# EASY_EDA_Neurostim.net
KiCad netlist of a schematic drawn in EasyEDA
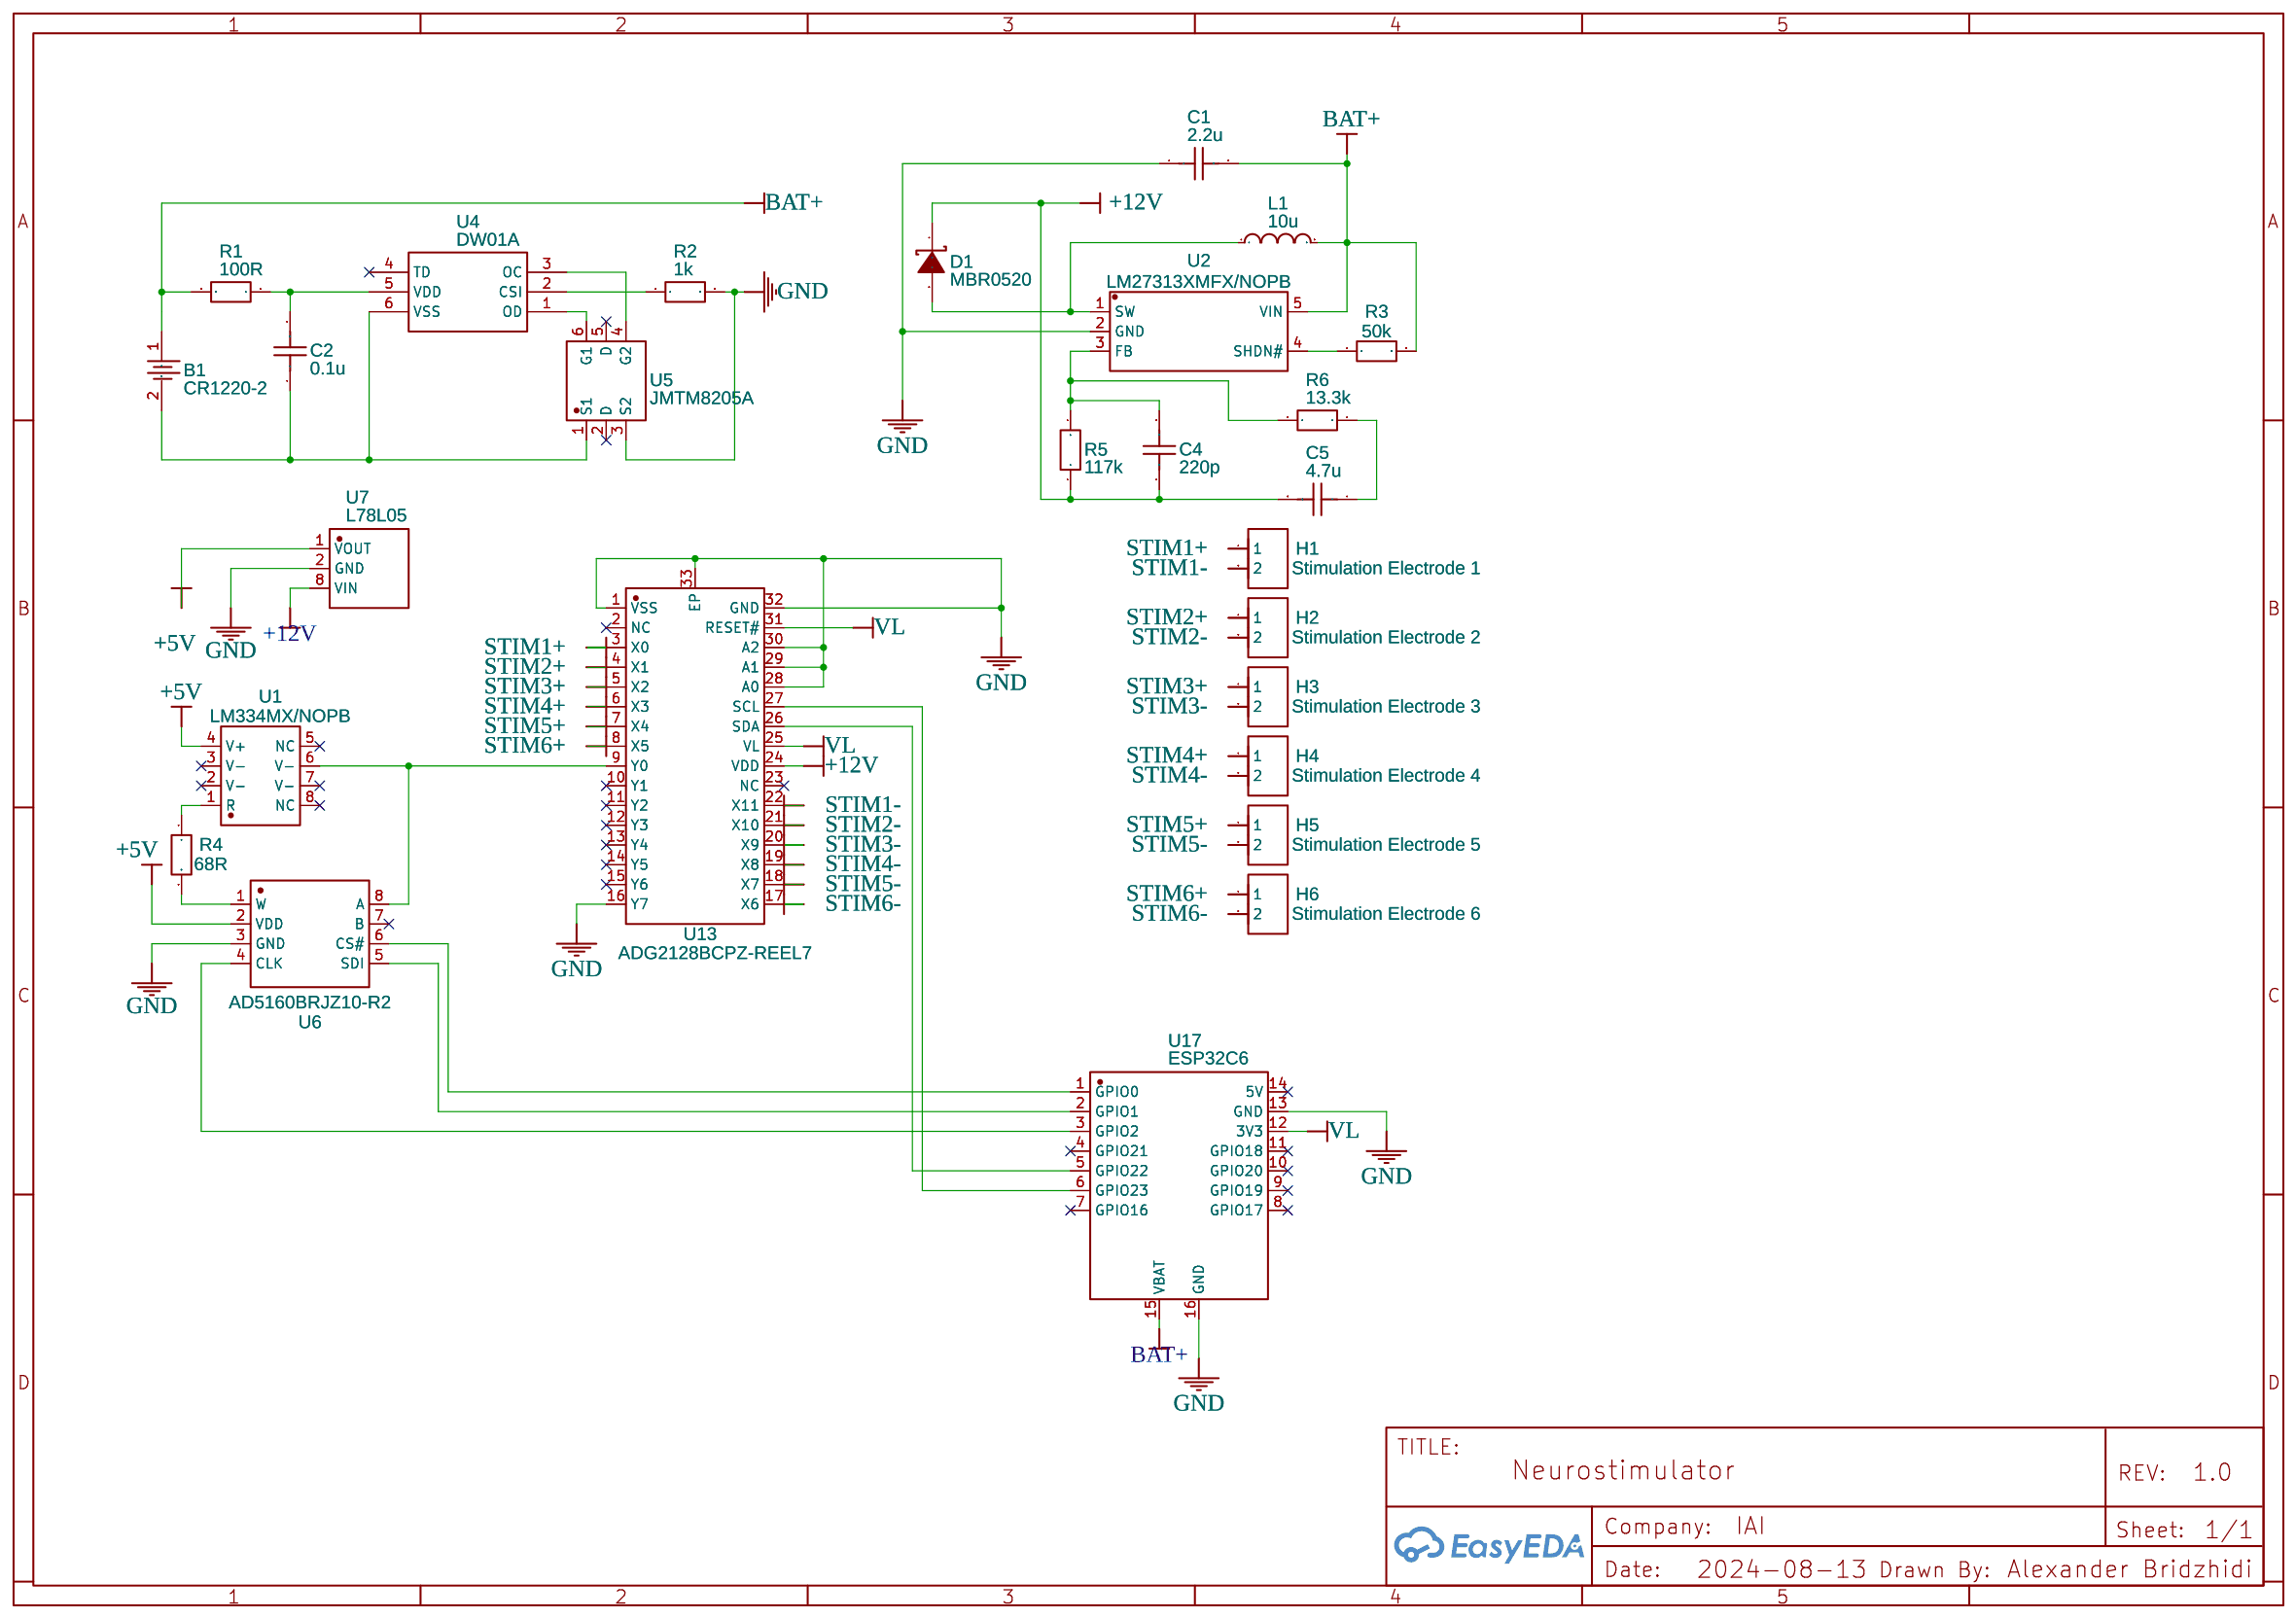
[diagram p0: 5V]
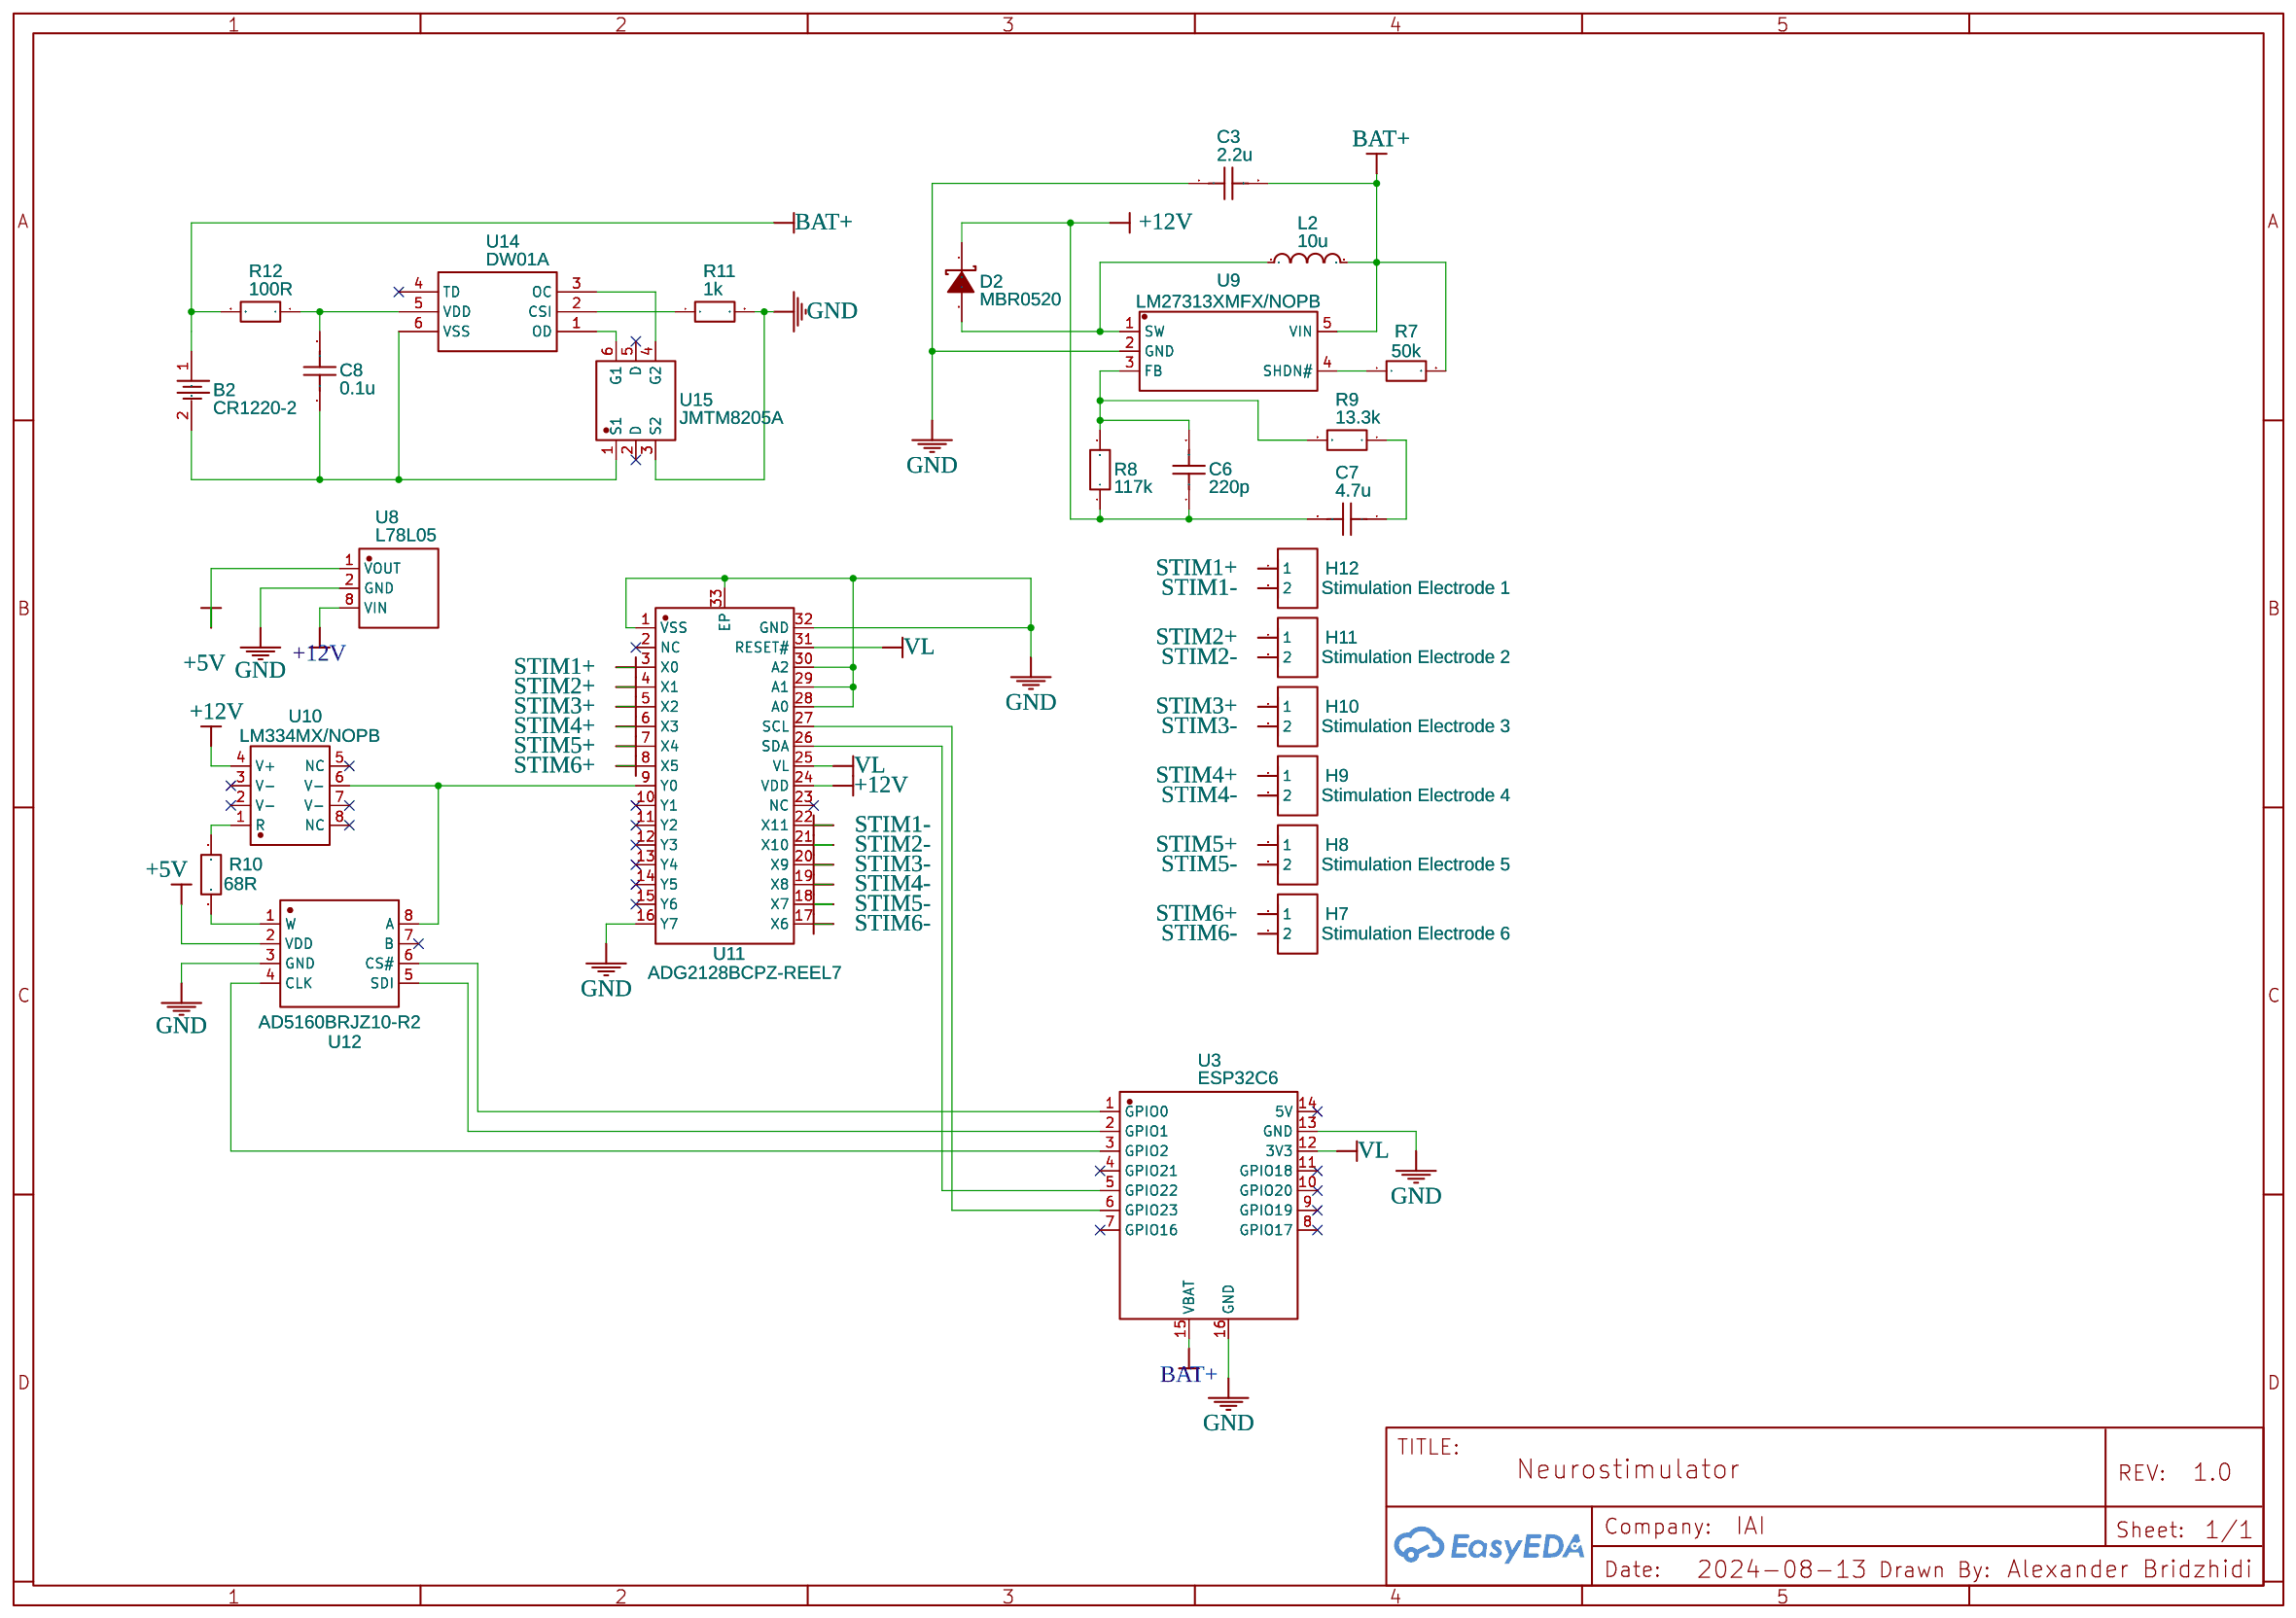
[diagram p1: 12V]

(export (version "E")
  (design (tool "Eeschema 10.0.6"))
  (components
    (comp (ref "B1")
      (value "CR1220-2")
      (fields (field (name "Manufacturer") "Q&J"))
      (libsource (lib "") (part "CR1220-2"))
    )
    (comp (ref "C1") (value "2.2u") (libsource (lib "") (part "C_0603_US_2")))
    (comp (ref "C2") (value "0.1u") (libsource (lib "") (part "C_0603_US")))
    (comp (ref "C4") (value "220p") (libsource (lib "") (part "C_0603_US")))
    (comp (ref "C5") (value "4.7u") (libsource (lib "") (part "C_0603_US_1")))
    (comp (ref "D1")
      (value "MBR0520")
      (fields (field (name "Manufacturer") "CJ(江苏长电/长晶)"))
      (libsource (lib "") (part "MBR0520"))
    )
    (comp (ref "H1") (value "Stimulation Electrode 1") (libsource (lib "") (part "HDR-F-2.54_1x2")))
    (comp (ref "H2") (value "Stimulation Electrode 2") (libsource (lib "") (part "HDR-F-2.54_1x2")))
    (comp (ref "H3") (value "Stimulation Electrode 3") (libsource (lib "") (part "HDR-F-2.54_1x2")))
    (comp (ref "H4") (value "Stimulation Electrode 4") (libsource (lib "") (part "HDR-F-2.54_1x2")))
    (comp (ref "H5") (value "Stimulation Electrode 5") (libsource (lib "") (part "HDR-F-2.54_1x2")))
    (comp (ref "H6") (value "Stimulation Electrode 6") (libsource (lib "") (part "HDR-F-2.54_1x2")))
    (comp (ref "L1") (value "10u") (libsource (lib "") (part "L0603_US")))
    (comp (ref "R1") (value "100R") (libsource (lib "") (part "R_0603_EU_1")))
    (comp (ref "R2") (value "1k") (libsource (lib "") (part "R_0603_EU_2")))
    (comp (ref "R3") (value "50k") (libsource (lib "") (part "R_0603_EU_2")))
    (comp (ref "R4") (value "68R") (libsource (lib "") (part "R_0805_EU")))
    (comp (ref "R5") (value "117k") (libsource (lib "") (part "R_0603_EU")))
    (comp (ref "R6") (value "13.3k") (libsource (lib "") (part "R_0603_EU_1")))
    (comp (ref "U1")
      (value "LM334MX/NOPB")
      (fields (field (name "Manufacturer") "TI(德州仪器)"))
      (libsource (lib "") (part "LM334MX/NOPB"))
    )
    (comp (ref "U2")
      (value "LM27313XMFX/NOPB")
      (fields (field (name "Manufacturer") "TI(德州仪器)"))
      (libsource (lib "") (part "LM27313XMFX/NOPB"))
    )
    (comp (ref "U4") (value "DW01A") (libsource (lib "") (part "DW01A")))
    (comp (ref "U5")
      (value "JMTM8205A")
      (fields (field (name "Manufacturer") "JJW(捷捷微)"))
      (libsource (lib "") (part "JMTM8205A"))
    )
    (comp (ref "U6")
      (value "AD5160BRJZ10-R2")
      (fields (field (name "Manufacturer") "ADI(亚德诺)"))
      (libsource (lib "") (part "AD5160BRJZ10-R2"))
    )
    (comp (ref "U7")
      (value "L78L05")
      (fields (field (name "Manufacturer Part") "L78L05ACZ-AP") (field (name "Manufacturer") "ST(意法半导体)"))
      (libsource (lib "") (part "L78L05ACZ-AP"))
    )
    (comp (ref "U13")
      (value "ADG2128BCPZ-REEL7")
      (fields (field (name "Manufacturer") "ADI(亚德诺)"))
      (libsource (lib "") (part "ADG2128BCPZ-REEL7"))
    )
    (comp (ref "U17") (value "ESP32C6") (libsource (lib "") (part "ESP32C6")))
    (comp (ref "B2")
      (value "CR1220-2")
      (fields (field (name "Manufacturer") "Q&J"))
      (libsource (lib "") (part "CR1220-2"))
    )
    (comp (ref "C3") (value "2.2u") (libsource (lib "") (part "C_0603_US_2")))
    (comp (ref "C6") (value "220p") (libsource (lib "") (part "C_0603_US_1")))
    (comp (ref "C7") (value "4.7u") (libsource (lib "") (part "C_0603_US")))
    (comp (ref "C8") (value "0.1u") (libsource (lib "") (part "C_0603_US_1")))
    (comp (ref "D2")
      (value "MBR0520")
      (fields (field (name "Manufacturer") "CJ(江苏长电/长晶)"))
      (libsource (lib "") (part "MBR0520"))
    )
    (comp (ref "H7") (value "Stimulation Electrode 6") (libsource (lib "") (part "HDR-F-2.54_1x2")))
    (comp (ref "H8") (value "Stimulation Electrode 5") (libsource (lib "") (part "HDR-F-2.54_1x2")))
    (comp (ref "H9") (value "Stimulation Electrode 4") (libsource (lib "") (part "HDR-F-2.54_1x2")))
    (comp (ref "H10") (value "Stimulation Electrode 3") (libsource (lib "") (part "HDR-F-2.54_1x2")))
    (comp (ref "H11") (value "Stimulation Electrode 2") (libsource (lib "") (part "HDR-F-2.54_1x2")))
    (comp (ref "H12") (value "Stimulation Electrode 1") (libsource (lib "") (part "HDR-F-2.54_1x2")))
    (comp (ref "L2") (value "10u") (libsource (lib "") (part "L0603_US")))
    (comp (ref "R7") (value "50k") (libsource (lib "") (part "R_0603_EU_1")))
    (comp (ref "R8") (value "117k") (libsource (lib "") (part "R_0603_EU_2")))
    (comp (ref "R9") (value "13.3k") (libsource (lib "") (part "R_0603_EU")))
    (comp (ref "R10") (value "68R") (libsource (lib "") (part "R_0805_EU")))
    (comp (ref "R11") (value "1k") (libsource (lib "") (part "R_0603_EU_1")))
    (comp (ref "R12") (value "100R") (libsource (lib "") (part "R_0603_EU")))
    (comp (ref "U3") (value "ESP32C6") (libsource (lib "") (part "ESP32C6")))
    (comp (ref "U8")
      (value "L78L05")
      (fields (field (name "Manufacturer Part") "L78L05ACZ-AP") (field (name "Manufacturer") "ST(意法半导体)"))
      (libsource (lib "") (part "L78L05ACZ-AP"))
    )
    (comp (ref "U9")
      (value "LM27313XMFX/NOPB")
      (fields (field (name "Manufacturer") "TI(德州仪器)"))
      (libsource (lib "") (part "LM27313XMFX/NOPB"))
    )
    (comp (ref "U10")
      (value "LM334MX/NOPB")
      (fields (field (name "Manufacturer") "TI(德州仪器)"))
      (libsource (lib "") (part "LM334MX/NOPB"))
    )
    (comp (ref "U11")
      (value "ADG2128BCPZ-REEL7")
      (fields (field (name "Manufacturer") "ADI(亚德诺)"))
      (libsource (lib "") (part "ADG2128BCPZ-REEL7"))
    )
    (comp (ref "U12")
      (value "AD5160BRJZ10-R2")
      (fields (field (name "Manufacturer") "ADI(亚德诺)"))
      (libsource (lib "") (part "AD5160BRJZ10-R2"))
    )
    (comp (ref "U14") (value "DW01A") (libsource (lib "") (part "DW01A")))
    (comp (ref "U15")
      (value "JMTM8205A")
      (fields (field (name "Manufacturer") "JJW(捷捷微)"))
      (libsource (lib "") (part "JMTM8205A"))
    )
  )
  (nets
    (net (code "1") (name "+5V") (class "Default")
      (node (ref "U1") (pin "4") (pinfunction "V+_4") (pintype "unspecified"))
      (node (ref "U12") (pin "2") (pinfunction "VDD_2") (pintype "unspecified"))
      (node (ref "U6") (pin "2") (pinfunction "VDD_2") (pintype "unspecified"))
      (node (ref "U7") (pin "1") (pinfunction "VOUT_1") (pintype "unspecified"))
      (node (ref "U8") (pin "1") (pinfunction "VOUT_1") (pintype "unspecified"))
    )
    (net (code "2") (name "+12V") (class "Default")
      (node (ref "C4") (pin "1") (pinfunction "1_1") (pintype "unspecified"))
      (node (ref "C5") (pin "2") (pinfunction "2_2") (pintype "unspecified"))
      (node (ref "C6") (pin "1") (pinfunction "1_1") (pintype "unspecified"))
      (node (ref "C7") (pin "2") (pinfunction "2_2") (pintype "unspecified"))
      (node (ref "D1") (pin "1") (pinfunction "K_1") (pintype "unspecified"))
      (node (ref "D2") (pin "1") (pinfunction "K_1") (pintype "unspecified"))
      (node (ref "R5") (pin "1") (pinfunction "1_1") (pintype "unspecified"))
      (node (ref "R8") (pin "1") (pinfunction "1_1") (pintype "unspecified"))
      (node (ref "U10") (pin "4") (pinfunction "V+_4") (pintype "unspecified"))
      (node (ref "U11") (pin "24") (pinfunction "VDD_24") (pintype "unspecified"))
      (node (ref "U13") (pin "24") (pinfunction "VDD_24") (pintype "unspecified"))
      (node (ref "U7") (pin "8") (pinfunction "VIN_8") (pintype "unspecified"))
      (node (ref "U8") (pin "8") (pinfunction "VIN_8") (pintype "unspecified"))
    )
    (net (code "3") (name "BAT+") (class "Default")
      (node (ref "B1") (pin "1") (pinfunction "1_1") (pintype "input"))
      (node (ref "B2") (pin "1") (pinfunction "1_1") (pintype "input"))
      (node (ref "C1") (pin "2") (pinfunction "2_2") (pintype "unspecified"))
      (node (ref "C3") (pin "2") (pinfunction "2_2") (pintype "unspecified"))
      (node (ref "L1") (pin "2") (pinfunction "2_2") (pintype "unspecified"))
      (node (ref "L2") (pin "2") (pinfunction "2_2") (pintype "unspecified"))
      (node (ref "R1") (pin "2") (pinfunction "2_2") (pintype "unspecified"))
      (node (ref "R12") (pin "2") (pinfunction "2_2") (pintype "unspecified"))
      (node (ref "R3") (pin "2") (pinfunction "2_2") (pintype "unspecified"))
      (node (ref "R7") (pin "2") (pinfunction "2_2") (pintype "unspecified"))
      (node (ref "U17") (pin "15") (pinfunction "VBAT_15") (pintype "unspecified"))
      (node (ref "U2") (pin "5") (pinfunction "VIN_5") (pintype "unspecified"))
      (node (ref "U3") (pin "15") (pinfunction "VBAT_15") (pintype "unspecified"))
      (node (ref "U9") (pin "5") (pinfunction "VIN_5") (pintype "unspecified"))
    )
    (net (code "4") (name "GND") (class "Default")
      (node (ref "C1") (pin "1") (pinfunction "1_1") (pintype "unspecified"))
      (node (ref "C3") (pin "1") (pinfunction "1_1") (pintype "unspecified"))
      (node (ref "R11") (pin "2") (pinfunction "2_2") (pintype "unspecified"))
      (node (ref "R2") (pin "2") (pinfunction "2_2") (pintype "unspecified"))
      (node (ref "U11") (pin "1") (pinfunction "VSS_1") (pintype "unspecified"))
      (node (ref "U11") (pin "16") (pinfunction "Y7_16") (pintype "unspecified"))
      (node (ref "U11") (pin "28") (pinfunction "A0_28") (pintype "unspecified"))
      (node (ref "U11") (pin "29") (pinfunction "A1_29") (pintype "unspecified"))
      (node (ref "U11") (pin "30") (pinfunction "A2_30") (pintype "unspecified"))
      (node (ref "U11") (pin "32") (pinfunction "GND_32") (pintype "unspecified"))
      (node (ref "U11") (pin "33") (pinfunction "EP_33") (pintype "unspecified"))
      (node (ref "U12") (pin "3") (pinfunction "GND_3") (pintype "unspecified"))
      (node (ref "U13") (pin "1") (pinfunction "VSS_1") (pintype "unspecified"))
      (node (ref "U13") (pin "16") (pinfunction "Y7_16") (pintype "unspecified"))
      (node (ref "U13") (pin "28") (pinfunction "A0_28") (pintype "unspecified"))
      (node (ref "U13") (pin "29") (pinfunction "A1_29") (pintype "unspecified"))
      (node (ref "U13") (pin "30") (pinfunction "A2_30") (pintype "unspecified"))
      (node (ref "U13") (pin "32") (pinfunction "GND_32") (pintype "unspecified"))
      (node (ref "U13") (pin "33") (pinfunction "EP_33") (pintype "unspecified"))
      (node (ref "U15") (pin "3") (pinfunction "S2_3") (pintype "unspecified"))
      (node (ref "U17") (pin "13") (pinfunction "GND_13") (pintype "unspecified"))
      (node (ref "U17") (pin "16") (pinfunction "GND_16") (pintype "unspecified"))
      (node (ref "U2") (pin "2") (pinfunction "GND_2") (pintype "unspecified"))
      (node (ref "U3") (pin "13") (pinfunction "GND_13") (pintype "unspecified"))
      (node (ref "U3") (pin "16") (pinfunction "GND_16") (pintype "unspecified"))
      (node (ref "U5") (pin "3") (pinfunction "S2_3") (pintype "unspecified"))
      (node (ref "U6") (pin "3") (pinfunction "GND_3") (pintype "unspecified"))
      (node (ref "U7") (pin "2") (pinfunction "GND_2") (pintype "unspecified"))
      (node (ref "U8") (pin "2") (pinfunction "GND_2") (pintype "unspecified"))
      (node (ref "U9") (pin "2") (pinfunction "GND_2") (pintype "unspecified"))
    )
    (net (code "5") (name "Net-(C5-Pad1)") (class "Default")
      (node (ref "C5") (pin "1") (pinfunction "1_1") (pintype "unspecified"))
      (node (ref "R6") (pin "1") (pinfunction "1_1") (pintype "unspecified"))
    )
    (net (code "6") (name "Net-(C7-Pad1)") (class "Default")
      (node (ref "C7") (pin "1") (pinfunction "1_1") (pintype "unspecified"))
      (node (ref "R9") (pin "1") (pinfunction "1_1") (pintype "unspecified"))
    )
    (net (code "7") (name "Net-(D1-A)") (class "Default")
      (node (ref "D1") (pin "2") (pinfunction "A_2") (pintype "unspecified"))
      (node (ref "L1") (pin "1") (pinfunction "1_1") (pintype "unspecified"))
      (node (ref "U2") (pin "1") (pinfunction "SW_1") (pintype "unspecified"))
    )
    (net (code "8") (name "Net-(D2-A)") (class "Default")
      (node (ref "D2") (pin "2") (pinfunction "A_2") (pintype "unspecified"))
      (node (ref "L2") (pin "1") (pinfunction "1_1") (pintype "unspecified"))
      (node (ref "U9") (pin "1") (pinfunction "SW_1") (pintype "unspecified"))
    )
    (net (code "9") (name "Net-(U1-R)") (class "Default")
      (node (ref "R4") (pin "1") (pinfunction "1_1") (pintype "unspecified"))
      (node (ref "U1") (pin "1") (pinfunction "R_1") (pintype "unspecified"))
    )
    (net (code "10") (name "Net-(U2-FB)") (class "Default")
      (node (ref "C4") (pin "2") (pinfunction "2_2") (pintype "unspecified"))
      (node (ref "R5") (pin "2") (pinfunction "2_2") (pintype "unspecified"))
      (node (ref "R6") (pin "2") (pinfunction "2_2") (pintype "unspecified"))
      (node (ref "U2") (pin "3") (pinfunction "FB_3") (pintype "unspecified"))
    )
    (net (code "11") (name "Net-(U2-SHDN#)") (class "Default")
      (node (ref "R3") (pin "1") (pinfunction "1_1") (pintype "unspecified"))
      (node (ref "U2") (pin "4") (pinfunction "SHDN#_4") (pintype "unspecified"))
    )
    (net (code "12") (name "Net-(U4-CSI)") (class "Default")
      (node (ref "R2") (pin "1") (pinfunction "1_1") (pintype "unspecified"))
      (node (ref "U4") (pin "2") (pinfunction "CSI_2") (pintype "unspecified"))
    )
    (net (code "13") (name "Net-(U4-OC)") (class "Default")
      (node (ref "U4") (pin "3") (pinfunction "OC_3") (pintype "unspecified"))
      (node (ref "U5") (pin "4") (pinfunction "G2_4") (pintype "unspecified"))
    )
    (net (code "14") (name "Net-(U4-OD)") (class "Default")
      (node (ref "U4") (pin "1") (pinfunction "OD_1") (pintype "unspecified"))
      (node (ref "U5") (pin "6") (pinfunction "G1_6") (pintype "unspecified"))
    )
    (net (code "15") (name "Net-(U4-VDD)") (class "Default")
      (node (ref "C2") (pin "2") (pinfunction "2_2") (pintype "unspecified"))
      (node (ref "R1") (pin "1") (pinfunction "1_1") (pintype "unspecified"))
      (node (ref "U4") (pin "5") (pinfunction "VDD_5") (pintype "unspecified"))
    )
    (net (code "16") (name "Net-(U4-VSS)") (class "Default")
      (node (ref "B1") (pin "2") (pinfunction "2_2") (pintype "input"))
      (node (ref "C2") (pin "1") (pinfunction "1_1") (pintype "unspecified"))
      (node (ref "U4") (pin "6") (pinfunction "VSS_6") (pintype "unspecified"))
      (node (ref "U5") (pin "1") (pinfunction "S1_1") (pintype "unspecified"))
    )
    (net (code "17") (name "Net-(U6-W)") (class "Default")
      (node (ref "R4") (pin "2") (pinfunction "2_2") (pintype "unspecified"))
      (node (ref "U6") (pin "1") (pinfunction "W_1") (pintype "unspecified"))
    )
    (net (code "18") (name "Net-(U9-FB)") (class "Default")
      (node (ref "C6") (pin "2") (pinfunction "2_2") (pintype "unspecified"))
      (node (ref "R8") (pin "2") (pinfunction "2_2") (pintype "unspecified"))
      (node (ref "R9") (pin "2") (pinfunction "2_2") (pintype "unspecified"))
      (node (ref "U9") (pin "3") (pinfunction "FB_3") (pintype "unspecified"))
    )
    (net (code "19") (name "Net-(U9-SHDN#)") (class "Default")
      (node (ref "R7") (pin "1") (pinfunction "1_1") (pintype "unspecified"))
      (node (ref "U9") (pin "4") (pinfunction "SHDN#_4") (pintype "unspecified"))
    )
    (net (code "20") (name "Net-(U10-R)") (class "Default")
      (node (ref "R10") (pin "1") (pinfunction "1_1") (pintype "unspecified"))
      (node (ref "U10") (pin "1") (pinfunction "R_1") (pintype "unspecified"))
    )
    (net (code "21") (name "Net-(U11-SCL)") (class "Default")
      (node (ref "U11") (pin "27") (pinfunction "SCL_27") (pintype "unspecified"))
      (node (ref "U3") (pin "6") (pinfunction "GPIO23_6") (pintype "unspecified"))
    )
    (net (code "22") (name "Net-(U11-SDA)") (class "Default")
      (node (ref "U11") (pin "26") (pinfunction "SDA_26") (pintype "unspecified"))
      (node (ref "U3") (pin "5") (pinfunction "GPIO22_5") (pintype "unspecified"))
    )
    (net (code "23") (name "Net-(U11-Y0)") (class "Default")
      (node (ref "U10") (pin "6") (pinfunction "V-_6") (pintype "unspecified"))
      (node (ref "U11") (pin "9") (pinfunction "Y0_9") (pintype "unspecified"))
      (node (ref "U12") (pin "8") (pinfunction "A_8") (pintype "unspecified"))
    )
    (net (code "24") (name "Net-(U12-CLK)") (class "Default")
      (node (ref "U12") (pin "4") (pinfunction "CLK_4") (pintype "unspecified"))
      (node (ref "U3") (pin "3") (pinfunction "GPIO2_3") (pintype "unspecified"))
    )
    (net (code "25") (name "Net-(U12-CS#)") (class "Default")
      (node (ref "U12") (pin "6") (pinfunction "CS#_6") (pintype "unspecified"))
      (node (ref "U3") (pin "1") (pinfunction "GPIO0_1") (pintype "unspecified"))
    )
    (net (code "26") (name "Net-(U12-SDI)") (class "Default")
      (node (ref "U12") (pin "5") (pinfunction "SDI_5") (pintype "unspecified"))
      (node (ref "U3") (pin "2") (pinfunction "GPIO1_2") (pintype "unspecified"))
    )
    (net (code "27") (name "Net-(U12-W)") (class "Default")
      (node (ref "R10") (pin "2") (pinfunction "2_2") (pintype "unspecified"))
      (node (ref "U12") (pin "1") (pinfunction "W_1") (pintype "unspecified"))
    )
    (net (code "28") (name "Net-(U13-SCL)") (class "Default")
      (node (ref "U13") (pin "27") (pinfunction "SCL_27") (pintype "unspecified"))
      (node (ref "U17") (pin "6") (pinfunction "GPIO23_6") (pintype "unspecified"))
    )
    (net (code "29") (name "Net-(U13-SDA)") (class "Default")
      (node (ref "U13") (pin "26") (pinfunction "SDA_26") (pintype "unspecified"))
      (node (ref "U17") (pin "5") (pinfunction "GPIO22_5") (pintype "unspecified"))
    )
    (net (code "30") (name "Net-(U13-Y0)") (class "Default")
      (node (ref "U1") (pin "6") (pinfunction "V-_6") (pintype "unspecified"))
      (node (ref "U13") (pin "9") (pinfunction "Y0_9") (pintype "unspecified"))
      (node (ref "U6") (pin "8") (pinfunction "A_8") (pintype "unspecified"))
    )
    (net (code "31") (name "Net-(U14-CSI)") (class "Default")
      (node (ref "R11") (pin "1") (pinfunction "1_1") (pintype "unspecified"))
      (node (ref "U14") (pin "2") (pinfunction "CSI_2") (pintype "unspecified"))
    )
    (net (code "32") (name "Net-(U14-OC)") (class "Default")
      (node (ref "U14") (pin "3") (pinfunction "OC_3") (pintype "unspecified"))
      (node (ref "U15") (pin "4") (pinfunction "G2_4") (pintype "unspecified"))
    )
    (net (code "33") (name "Net-(U14-OD)") (class "Default")
      (node (ref "U14") (pin "1") (pinfunction "OD_1") (pintype "unspecified"))
      (node (ref "U15") (pin "6") (pinfunction "G1_6") (pintype "unspecified"))
    )
    (net (code "34") (name "Net-(U14-VDD)") (class "Default")
      (node (ref "C8") (pin "2") (pinfunction "2_2") (pintype "unspecified"))
      (node (ref "R12") (pin "1") (pinfunction "1_1") (pintype "unspecified"))
      (node (ref "U14") (pin "5") (pinfunction "VDD_5") (pintype "unspecified"))
    )
    (net (code "35") (name "Net-(U14-VSS)") (class "Default")
      (node (ref "B2") (pin "2") (pinfunction "2_2") (pintype "input"))
      (node (ref "C8") (pin "1") (pinfunction "1_1") (pintype "unspecified"))
      (node (ref "U14") (pin "6") (pinfunction "VSS_6") (pintype "unspecified"))
      (node (ref "U15") (pin "1") (pinfunction "S1_1") (pintype "unspecified"))
    )
    (net (code "36") (name "Net-(U17-GPIO0)") (class "Default")
      (node (ref "U17") (pin "1") (pinfunction "GPIO0_1") (pintype "unspecified"))
      (node (ref "U6") (pin "6") (pinfunction "CS#_6") (pintype "unspecified"))
    )
    (net (code "37") (name "Net-(U17-GPIO1)") (class "Default")
      (node (ref "U17") (pin "2") (pinfunction "GPIO1_2") (pintype "unspecified"))
      (node (ref "U6") (pin "5") (pinfunction "SDI_5") (pintype "unspecified"))
    )
    (net (code "38") (name "Net-(U17-GPIO2)") (class "Default")
      (node (ref "U17") (pin "3") (pinfunction "GPIO2_3") (pintype "unspecified"))
      (node (ref "U6") (pin "4") (pinfunction "CLK_4") (pintype "unspecified"))
    )
    (net (code "39") (name "STIM1+") (class "Default")
      (node (ref "H1") (pin "1") (pinfunction "1_1") (pintype "input"))
      (node (ref "H12") (pin "1") (pinfunction "1_1") (pintype "input"))
      (node (ref "U11") (pin "3") (pinfunction "X0_3") (pintype "unspecified"))
      (node (ref "U13") (pin "3") (pinfunction "X0_3") (pintype "unspecified"))
    )
    (net (code "40") (name "STIM1-") (class "Default")
      (node (ref "H1") (pin "2") (pinfunction "2_2") (pintype "input"))
      (node (ref "H12") (pin "2") (pinfunction "2_2") (pintype "input"))
      (node (ref "U11") (pin "22") (pinfunction "X11_22") (pintype "unspecified"))
      (node (ref "U13") (pin "22") (pinfunction "X11_22") (pintype "unspecified"))
    )
    (net (code "41") (name "STIM2+") (class "Default")
      (node (ref "H11") (pin "1") (pinfunction "1_1") (pintype "input"))
      (node (ref "H2") (pin "1") (pinfunction "1_1") (pintype "input"))
      (node (ref "U11") (pin "4") (pinfunction "X1_4") (pintype "unspecified"))
      (node (ref "U13") (pin "4") (pinfunction "X1_4") (pintype "unspecified"))
    )
    (net (code "42") (name "STIM2-") (class "Default")
      (node (ref "H11") (pin "2") (pinfunction "2_2") (pintype "input"))
      (node (ref "H2") (pin "2") (pinfunction "2_2") (pintype "input"))
      (node (ref "U11") (pin "21") (pinfunction "X10_21") (pintype "unspecified"))
      (node (ref "U13") (pin "21") (pinfunction "X10_21") (pintype "unspecified"))
    )
    (net (code "43") (name "STIM3+") (class "Default")
      (node (ref "H10") (pin "1") (pinfunction "1_1") (pintype "input"))
      (node (ref "H3") (pin "1") (pinfunction "1_1") (pintype "input"))
      (node (ref "U11") (pin "5") (pinfunction "X2_5") (pintype "unspecified"))
      (node (ref "U13") (pin "5") (pinfunction "X2_5") (pintype "unspecified"))
    )
    (net (code "44") (name "STIM3-") (class "Default")
      (node (ref "H10") (pin "2") (pinfunction "2_2") (pintype "input"))
      (node (ref "H3") (pin "2") (pinfunction "2_2") (pintype "input"))
      (node (ref "U11") (pin "20") (pinfunction "X9_20") (pintype "unspecified"))
      (node (ref "U13") (pin "20") (pinfunction "X9_20") (pintype "unspecified"))
    )
    (net (code "45") (name "STIM4+") (class "Default")
      (node (ref "H4") (pin "1") (pinfunction "1_1") (pintype "input"))
      (node (ref "H9") (pin "1") (pinfunction "1_1") (pintype "input"))
      (node (ref "U11") (pin "6") (pinfunction "X3_6") (pintype "unspecified"))
      (node (ref "U13") (pin "6") (pinfunction "X3_6") (pintype "unspecified"))
    )
    (net (code "46") (name "STIM4-") (class "Default")
      (node (ref "H4") (pin "2") (pinfunction "2_2") (pintype "input"))
      (node (ref "H9") (pin "2") (pinfunction "2_2") (pintype "input"))
      (node (ref "U11") (pin "19") (pinfunction "X8_19") (pintype "unspecified"))
      (node (ref "U13") (pin "19") (pinfunction "X8_19") (pintype "unspecified"))
    )
    (net (code "47") (name "STIM5+") (class "Default")
      (node (ref "H5") (pin "1") (pinfunction "1_1") (pintype "input"))
      (node (ref "H8") (pin "1") (pinfunction "1_1") (pintype "input"))
      (node (ref "U11") (pin "7") (pinfunction "X4_7") (pintype "unspecified"))
      (node (ref "U13") (pin "7") (pinfunction "X4_7") (pintype "unspecified"))
    )
    (net (code "48") (name "STIM5-") (class "Default")
      (node (ref "H5") (pin "2") (pinfunction "2_2") (pintype "input"))
      (node (ref "H8") (pin "2") (pinfunction "2_2") (pintype "input"))
      (node (ref "U11") (pin "18") (pinfunction "X7_18") (pintype "unspecified"))
      (node (ref "U13") (pin "18") (pinfunction "X7_18") (pintype "unspecified"))
    )
    (net (code "49") (name "STIM6+") (class "Default")
      (node (ref "H6") (pin "1") (pinfunction "1_1") (pintype "input"))
      (node (ref "H7") (pin "1") (pinfunction "1_1") (pintype "input"))
      (node (ref "U11") (pin "8") (pinfunction "X5_8") (pintype "unspecified"))
      (node (ref "U13") (pin "8") (pinfunction "X5_8") (pintype "unspecified"))
    )
    (net (code "50") (name "STIM6-") (class "Default")
      (node (ref "H6") (pin "2") (pinfunction "2_2") (pintype "input"))
      (node (ref "H7") (pin "2") (pinfunction "2_2") (pintype "input"))
      (node (ref "U11") (pin "17") (pinfunction "X6_17") (pintype "unspecified"))
      (node (ref "U13") (pin "17") (pinfunction "X6_17") (pintype "unspecified"))
    )
    (net (code "51") (name "VL") (class "Default")
      (node (ref "U11") (pin "25") (pinfunction "VL_25") (pintype "unspecified"))
      (node (ref "U11") (pin "31") (pinfunction "RESET#_31") (pintype "unspecified"))
      (node (ref "U13") (pin "25") (pinfunction "VL_25") (pintype "unspecified"))
      (node (ref "U13") (pin "31") (pinfunction "RESET#_31") (pintype "unspecified"))
      (node (ref "U17") (pin "12") (pinfunction "3V3_12") (pintype "unspecified"))
      (node (ref "U3") (pin "12") (pinfunction "3V3_12") (pintype "unspecified"))
    )
    (net (code "52") (name "unconnected-(U1-NC-Pad5)") (class "Default")
      (node (ref "U1") (pin "5") (pinfunction "NC_5") (pintype "unspecified+no_connect"))
    )
    (net (code "53") (name "unconnected-(U1-NC-Pad8)") (class "Default")
      (node (ref "U1") (pin "8") (pinfunction "NC_8") (pintype "unspecified+no_connect"))
    )
    (net (code "54") (name "unconnected-(U1-V--Pad2)") (class "Default")
      (node (ref "U1") (pin "2") (pinfunction "V-_2") (pintype "unspecified+no_connect"))
    )
    (net (code "55") (name "unconnected-(U1-V--Pad3)") (class "Default")
      (node (ref "U1") (pin "3") (pinfunction "V-_3") (pintype "unspecified+no_connect"))
    )
    (net (code "56") (name "unconnected-(U1-V--Pad7)") (class "Default")
      (node (ref "U1") (pin "7") (pinfunction "V-_7") (pintype "unspecified+no_connect"))
    )
    (net (code "57") (name "unconnected-(U3-5V-Pad14)") (class "Default")
      (node (ref "U3") (pin "14") (pinfunction "5V_14") (pintype "unspecified+no_connect"))
    )
    (net (code "58") (name "unconnected-(U3-GPIO16-Pad7)") (class "Default")
      (node (ref "U3") (pin "7") (pinfunction "GPIO16_7") (pintype "unspecified+no_connect"))
    )
    (net (code "59") (name "unconnected-(U3-GPIO17-Pad8)") (class "Default")
      (node (ref "U3") (pin "8") (pinfunction "GPIO17_8") (pintype "unspecified+no_connect"))
    )
    (net (code "60") (name "unconnected-(U3-GPIO18-Pad11)") (class "Default")
      (node (ref "U3") (pin "11") (pinfunction "GPIO18_11") (pintype "unspecified+no_connect"))
    )
    (net (code "61") (name "unconnected-(U3-GPIO19-Pad9)") (class "Default")
      (node (ref "U3") (pin "9") (pinfunction "GPIO19_9") (pintype "unspecified+no_connect"))
    )
    (net (code "62") (name "unconnected-(U3-GPIO20-Pad10)") (class "Default")
      (node (ref "U3") (pin "10") (pinfunction "GPIO20_10") (pintype "unspecified+no_connect"))
    )
    (net (code "63") (name "unconnected-(U3-GPIO21-Pad4)") (class "Default")
      (node (ref "U3") (pin "4") (pinfunction "GPIO21_4") (pintype "unspecified+no_connect"))
    )
    (net (code "64") (name "unconnected-(U4-TD-Pad4)") (class "Default")
      (node (ref "U4") (pin "4") (pinfunction "TD_4") (pintype "unspecified+no_connect"))
    )
    (net (code "65") (name "unconnected-(U5-D-Pad2)") (class "Default")
      (node (ref "U5") (pin "2") (pinfunction "D_2") (pintype "unspecified+no_connect"))
    )
    (net (code "66") (name "unconnected-(U5-D-Pad5)") (class "Default")
      (node (ref "U5") (pin "5") (pinfunction "D_5") (pintype "unspecified+no_connect"))
    )
    (net (code "67") (name "unconnected-(U6-B-Pad7)") (class "Default")
      (node (ref "U6") (pin "7") (pinfunction "B_7") (pintype "unspecified+no_connect"))
    )
    (net (code "68") (name "unconnected-(U10-NC-Pad5)") (class "Default")
      (node (ref "U10") (pin "5") (pinfunction "NC_5") (pintype "unspecified+no_connect"))
    )
    (net (code "69") (name "unconnected-(U10-NC-Pad8)") (class "Default")
      (node (ref "U10") (pin "8") (pinfunction "NC_8") (pintype "unspecified+no_connect"))
    )
    (net (code "70") (name "unconnected-(U10-V--Pad2)") (class "Default")
      (node (ref "U10") (pin "2") (pinfunction "V-_2") (pintype "unspecified+no_connect"))
    )
    (net (code "71") (name "unconnected-(U10-V--Pad3)") (class "Default")
      (node (ref "U10") (pin "3") (pinfunction "V-_3") (pintype "unspecified+no_connect"))
    )
    (net (code "72") (name "unconnected-(U10-V--Pad7)") (class "Default")
      (node (ref "U10") (pin "7") (pinfunction "V-_7") (pintype "unspecified+no_connect"))
    )
    (net (code "73") (name "unconnected-(U11-NC-Pad2)") (class "Default")
      (node (ref "U11") (pin "2") (pinfunction "NC_2") (pintype "unspecified+no_connect"))
    )
    (net (code "74") (name "unconnected-(U11-NC-Pad23)") (class "Default")
      (node (ref "U11") (pin "23") (pinfunction "NC_23") (pintype "unspecified+no_connect"))
    )
    (net (code "75") (name "unconnected-(U11-Y1-Pad10)") (class "Default")
      (node (ref "U11") (pin "10") (pinfunction "Y1_10") (pintype "unspecified+no_connect"))
    )
    (net (code "76") (name "unconnected-(U11-Y2-Pad11)") (class "Default")
      (node (ref "U11") (pin "11") (pinfunction "Y2_11") (pintype "unspecified+no_connect"))
    )
    (net (code "77") (name "unconnected-(U11-Y3-Pad12)") (class "Default")
      (node (ref "U11") (pin "12") (pinfunction "Y3_12") (pintype "unspecified+no_connect"))
    )
    (net (code "78") (name "unconnected-(U11-Y4-Pad13)") (class "Default")
      (node (ref "U11") (pin "13") (pinfunction "Y4_13") (pintype "unspecified+no_connect"))
    )
    (net (code "79") (name "unconnected-(U11-Y5-Pad14)") (class "Default")
      (node (ref "U11") (pin "14") (pinfunction "Y5_14") (pintype "unspecified+no_connect"))
    )
    (net (code "80") (name "unconnected-(U11-Y6-Pad15)") (class "Default")
      (node (ref "U11") (pin "15") (pinfunction "Y6_15") (pintype "unspecified+no_connect"))
    )
    (net (code "81") (name "unconnected-(U12-B-Pad7)") (class "Default")
      (node (ref "U12") (pin "7") (pinfunction "B_7") (pintype "unspecified+no_connect"))
    )
    (net (code "82") (name "unconnected-(U13-NC-Pad2)") (class "Default")
      (node (ref "U13") (pin "2") (pinfunction "NC_2") (pintype "unspecified+no_connect"))
    )
    (net (code "83") (name "unconnected-(U13-NC-Pad23)") (class "Default")
      (node (ref "U13") (pin "23") (pinfunction "NC_23") (pintype "unspecified+no_connect"))
    )
    (net (code "84") (name "unconnected-(U13-Y1-Pad10)") (class "Default")
      (node (ref "U13") (pin "10") (pinfunction "Y1_10") (pintype "unspecified+no_connect"))
    )
    (net (code "85") (name "unconnected-(U13-Y2-Pad11)") (class "Default")
      (node (ref "U13") (pin "11") (pinfunction "Y2_11") (pintype "unspecified+no_connect"))
    )
    (net (code "86") (name "unconnected-(U13-Y3-Pad12)") (class "Default")
      (node (ref "U13") (pin "12") (pinfunction "Y3_12") (pintype "unspecified+no_connect"))
    )
    (net (code "87") (name "unconnected-(U13-Y4-Pad13)") (class "Default")
      (node (ref "U13") (pin "13") (pinfunction "Y4_13") (pintype "unspecified+no_connect"))
    )
    (net (code "88") (name "unconnected-(U13-Y5-Pad14)") (class "Default")
      (node (ref "U13") (pin "14") (pinfunction "Y5_14") (pintype "unspecified+no_connect"))
    )
    (net (code "89") (name "unconnected-(U13-Y6-Pad15)") (class "Default")
      (node (ref "U13") (pin "15") (pinfunction "Y6_15") (pintype "unspecified+no_connect"))
    )
    (net (code "90") (name "unconnected-(U14-TD-Pad4)") (class "Default")
      (node (ref "U14") (pin "4") (pinfunction "TD_4") (pintype "unspecified+no_connect"))
    )
    (net (code "91") (name "unconnected-(U15-D-Pad2)") (class "Default")
      (node (ref "U15") (pin "2") (pinfunction "D_2") (pintype "unspecified+no_connect"))
    )
    (net (code "92") (name "unconnected-(U15-D-Pad5)") (class "Default")
      (node (ref "U15") (pin "5") (pinfunction "D_5") (pintype "unspecified+no_connect"))
    )
    (net (code "93") (name "unconnected-(U17-5V-Pad14)") (class "Default")
      (node (ref "U17") (pin "14") (pinfunction "5V_14") (pintype "unspecified+no_connect"))
    )
    (net (code "94") (name "unconnected-(U17-GPIO16-Pad7)") (class "Default")
      (node (ref "U17") (pin "7") (pinfunction "GPIO16_7") (pintype "unspecified+no_connect"))
    )
    (net (code "95") (name "unconnected-(U17-GPIO17-Pad8)") (class "Default")
      (node (ref "U17") (pin "8") (pinfunction "GPIO17_8") (pintype "unspecified+no_connect"))
    )
    (net (code "96") (name "unconnected-(U17-GPIO18-Pad11)") (class "Default")
      (node (ref "U17") (pin "11") (pinfunction "GPIO18_11") (pintype "unspecified+no_connect"))
    )
    (net (code "97") (name "unconnected-(U17-GPIO19-Pad9)") (class "Default")
      (node (ref "U17") (pin "9") (pinfunction "GPIO19_9") (pintype "unspecified+no_connect"))
    )
    (net (code "98") (name "unconnected-(U17-GPIO20-Pad10)") (class "Default")
      (node (ref "U17") (pin "10") (pinfunction "GPIO20_10") (pintype "unspecified+no_connect"))
    )
    (net (code "99") (name "unconnected-(U17-GPIO21-Pad4)") (class "Default")
      (node (ref "U17") (pin "4") (pinfunction "GPIO21_4") (pintype "unspecified+no_connect"))
    )
  )
)
